# MCPS_Supply_030601.net
KiCad netlist of a schematic drawn in Altium Designer
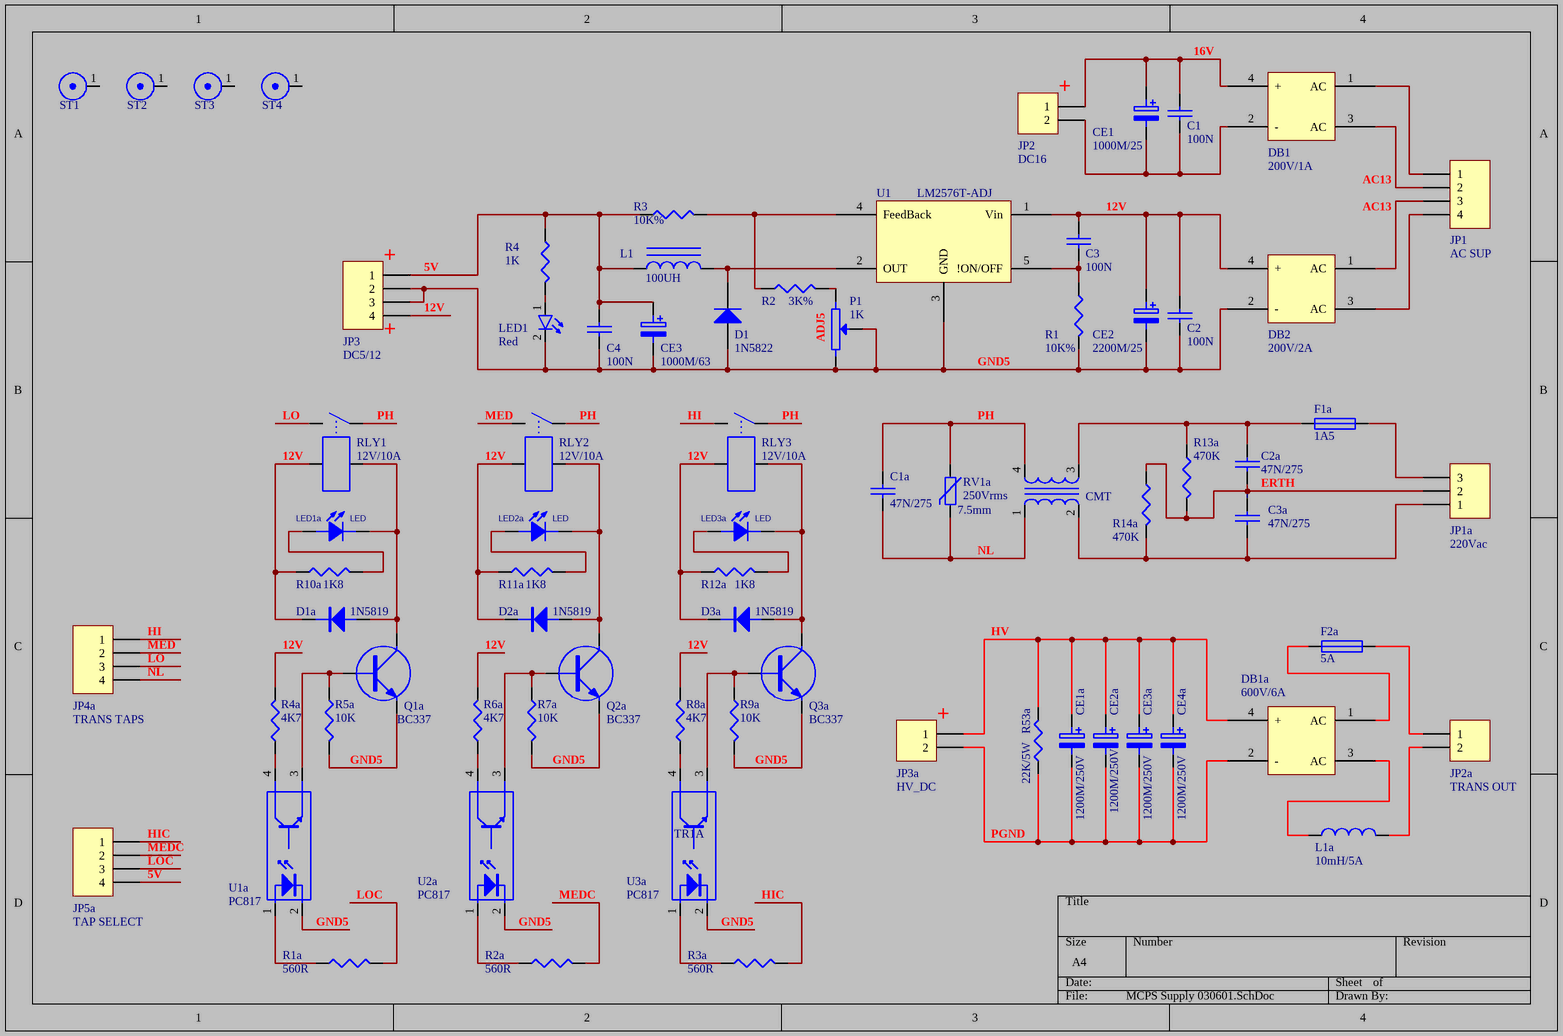
[diagram p0: MCPS Supply 030601.SchDoc]

(export (version "E")
  (design (tool "Eeschema 10.0.6"))
  (components
    (comp (ref "C1") (value "100N") (footprint "c1.8p") (libsource (lib "*") (part "C")))
    (comp (ref "C1a") (value "47N/275") (footprint "47N/275") (libsource (lib "*") (part "C")))
    (comp (ref "C2") (value "100N") (footprint "c1.8p") (libsource (lib "*") (part "C")))
    (comp (ref "C2a") (value "47N/275") (footprint "47N/275") (libsource (lib "*") (part "C")))
    (comp (ref "C3") (value "100N") (footprint "C3P") (libsource (lib "*") (part "C")))
    (comp (ref "C3a") (value "47N/275") (footprint "47N/275") (libsource (lib "*") (part "C")))
    (comp (ref "C4") (value "100N") (footprint "c1.8p") (libsource (lib "*") (part "C")))
    (comp (ref "CE1") (value "1000M/25") (footprint "CAP1000M/25V") (libsource (lib "*") (part "E")))
    (comp (ref "CE1a") (value "1200M/250V") (footprint "CAP 1200M/250") (libsource (lib "*") (part "E")))
    (comp (ref "CE2") (value "2200M/25") (footprint "CAP 2200/25") (libsource (lib "*") (part "E")))
    (comp (ref "CE2a") (value "1200M/250V") (footprint "CAP 1200M/250") (libsource (lib "*") (part "E")))
    (comp (ref "CE3") (value "1000M/63") (footprint "CAP2P") (libsource (lib "*") (part "E")))
    (comp (ref "CE3a") (value "1200M/250V") (footprint "CAP 1200M/250") (libsource (lib "*") (part "E")))
    (comp (ref "CE4a") (value "1200M/250V") (footprint "CAP 1200M/250") (libsource (lib "*") (part "E")))
    (comp (ref "D1")
      (value "1N5822")
      (footprint "d54")
      (description "Default Diode")
      (fields (field (name "PUBLISHER") "Altium Limited"))
      (libsource (lib "Miscellaneous Devices") (part "Diode"))
    )
    (comp (ref "D1a") (value "1N5819") (footprint "D4P") (libsource (lib "MyAltiumLib9702") (part "D")))
    (comp (ref "D2a") (value "1N5819") (footprint "D4P") (libsource (lib "MyAltiumLib9702") (part "D")))
    (comp (ref "D3a") (value "1N5819") (footprint "D4P") (libsource (lib "MyAltiumLib9702") (part "D")))
    (comp (ref "DB1")
      (value "200V/1A")
      (footprint "BRG 1A")
      (libsource (lib "1402 Schlib 2020") (part "BRIDGE"))
    )
    (comp (ref "DB1a")
      (value "600V/6A")
      (footprint "BRIDGE 6A")
      (libsource (lib "1403 Schlib 2020") (part "BRIDGE"))
    )
    (comp (ref "DB2")
      (value "200V/2A")
      (footprint "BRG GBU")
      (libsource (lib "1402 Schlib 2020") (part "BRIDGE"))
    )
    (comp (ref "F1a") (value "1A5") (footprint "FS") (libsource (lib "1402 Schlib 2020") (part "FUSE1")))
    (comp (ref "F2a") (value "5A") (footprint "FS") (libsource (lib "1402 Schlib 2020") (part "FUSE1")))
    (comp (ref "JP1")
      (value "AC SUP")
      (footprint "4EDG")
      (description "Header, 4-Pin")
      (fields (field (name "PUBLISHER") "Altium Limited"))
      (libsource (lib "") (part "Header 4_1"))
    )
    (comp (ref "JP1a")
      (value "220Vac")
      (footprint "3EDG-STR")
      (description "Header, 3-Pin")
      (fields (field (name "PUBLISHER") "Altium Limited"))
      (libsource (lib "1402 Schlib 2020") (part "Header 3"))
    )
    (comp (ref "JP2")
      (value "DC16")
      (footprint "2edg-str")
      (description "Header, 2-Pin")
      (fields (field (name "PUBLISHER") "Altium Limited"))
      (libsource (lib "") (part "Header 2_1"))
    )
    (comp (ref "JP2a")
      (value "TRANS OUT")
      (footprint "2edg-str")
      (description "Header, 2-Pin")
      (fields (field (name "PUBLISHER") "Altium Limited"))
      (libsource (lib "Miscellaneous Connectors") (part "Header 2"))
    )
    (comp (ref "JP3")
      (value "DC5/12")
      (footprint "4EDG")
      (description "Header, 4-Pin")
      (fields (field (name "PUBLISHER") "Altium Limited"))
      (libsource (lib "1403 Schlib 2020") (part "Header 4"))
    )
    (comp (ref "JP3a")
      (value "HV_DC")
      (footprint "DG55X2")
      (description "Header, 2-Pin")
      (fields (field (name "PUBLISHER") "Altium Limited"))
      (libsource (lib "") (part "Header 2_1"))
    )
    (comp (ref "JP4a")
      (value "TRANS TAPS")
      (footprint "4EDG")
      (description "Header, 4-Pin")
      (fields (field (name "PUBLISHER") "Altium Limited"))
      (libsource (lib "1403 Schlib 2020") (part "Header 4"))
    )
    (comp (ref "JP5a")
      (value "TAP SELECT")
      (footprint "4EDG")
      (description "Header, 4-Pin")
      (fields (field (name "PUBLISHER") "Altium Limited"))
      (libsource (lib "1403 Schlib 2020") (part "Header 4"))
    )
    (comp (ref "L1") (value "100UH") (footprint "inductor 2512") (libsource (lib "*") (part "INDUCTOR IRON")))
    (comp (ref "L1a")
      (value "10mH/5A")
      (footprint "INDUCTOR 2208")
      (libsource (lib "MyAltiumLib9702") (part "INDUCTOR"))
    )
    (comp (ref "LED1")
      (value "Red")
      (footprint "LED-5mm")
      (description "LED")
      (fields (field (name "COLOR") "Red") (field (name "DESIGNER") "Saeid Jorablo"))
      (libsource (lib "My Library") (part "LED"))
    )
    (comp (ref "LED1a")
      (value "LED")
      (footprint "LED-5mm")
      (description "LED LIGHTING")
      (fields (field (name "DESIGNER") "Abbas Basereh"))
      (libsource (lib "1403 Schlib 2020") (part "LED"))
    )
    (comp (ref "LED2a")
      (value "LED")
      (footprint "LED-5mm")
      (description "LED LIGHTING")
      (fields (field (name "DESIGNER") "Abbas Basereh"))
      (libsource (lib "1403 Schlib 2020") (part "LED"))
    )
    (comp (ref "LED3a")
      (value "LED")
      (footprint "LED-5mm")
      (description "LED LIGHTING")
      (fields (field (name "DESIGNER") "Abbas Basereh"))
      (libsource (lib "1403 Schlib 2020") (part "LED"))
    )
    (comp (ref "P1")
      (value "1K")
      (footprint "pot multi turn")
      (libsource (lib "1402 Schlib 2020") (part "POT2"))
    )
    (comp (ref "Q1a") (value "BC337") (footprint "CBE-BC546") (libsource (lib "1403 Schlib 2020") (part "N")))
    (comp (ref "Q2a") (value "BC337") (footprint "CBE-BC546") (libsource (lib "1403 Schlib 2020") (part "N")))
    (comp (ref "Q3a") (value "BC337") (footprint "CBE-BC546") (libsource (lib "1403 Schlib 2020") (part "N")))
    (comp (ref "R1") (value "10K%") (footprint "R4P") (libsource (lib "*") (part "R")))
    (comp (ref "R1a") (value "560R") (footprint "R4P") (libsource (lib "*") (part "R")))
    (comp (ref "R2") (value "3K%") (footprint "R4P") (libsource (lib "*") (part "R")))
    (comp (ref "R2a") (value "560R") (footprint "R4P") (libsource (lib "*") (part "R")))
    (comp (ref "R3") (value "10K%") (footprint "R4P") (libsource (lib "*") (part "R")))
    (comp (ref "R3a") (value "560R") (footprint "R4P") (libsource (lib "*") (part "R")))
    (comp (ref "R4") (value "1K") (footprint "R4P") (libsource (lib "*") (part "R")))
    (comp (ref "R4a") (value "4K7") (footprint "R4P") (libsource (lib "*") (part "R")))
    (comp (ref "R5a") (value "10K") (footprint "R4P") (libsource (lib "*") (part "R")))
    (comp (ref "R6a") (value "4K7") (footprint "R4P") (libsource (lib "*") (part "R")))
    (comp (ref "R7a") (value "10K") (footprint "R4P") (libsource (lib "*") (part "R")))
    (comp (ref "R8a") (value "4K7") (footprint "R4P") (libsource (lib "*") (part "R")))
    (comp (ref "R9a") (value "10K") (footprint "R4P") (libsource (lib "*") (part "R")))
    (comp (ref "R10a") (value "1K8") (footprint "R4P") (libsource (lib "*") (part "R")))
    (comp (ref "R11a") (value "1K8") (footprint "R4P") (libsource (lib "*") (part "R")))
    (comp (ref "R12a") (value "1K8") (footprint "R4P") (libsource (lib "*") (part "R")))
    (comp (ref "R13a") (value "470K") (footprint "R5P") (libsource (lib "*") (part "R")))
    (comp (ref "R14a") (value "470K") (footprint "R5P") (libsource (lib "*") (part "R")))
    (comp (ref "R53a") (value "22K/5W") (footprint "R5W") (libsource (lib "*") (part "R")))
    (comp (ref "RLY1")
      (value "12V/10A")
      (footprint "RLY16D")
      (libsource (lib "1403 Schlib 2020") (part "RELAY-SPST4"))
    )
    (comp (ref "RLY2")
      (value "12V/10A")
      (footprint "RLY16D")
      (libsource (lib "1403 Schlib 2020") (part "RELAY-SPST4"))
    )
    (comp (ref "RLY3")
      (value "12V/10A")
      (footprint "RLY16D")
      (libsource (lib "1403 Schlib 2020") (part "RELAY-SPST4"))
    )
    (comp (ref "RV1a")
      (value "250Vrms")
      (footprint "VARISTOR 3")
      (libsource (lib "1402 Schlib 2020") (part "VARISTOR"))
    )
    (comp (ref "ST1") (value "STUD") (footprint "CORNER") (libsource (lib "1402 Schlib 2020") (part "STUD")))
    (comp (ref "ST2") (value "STUD") (footprint "CORNER") (libsource (lib "1402 Schlib 2020") (part "STUD")))
    (comp (ref "ST3") (value "STUD") (footprint "CORNER") (libsource (lib "1402 Schlib 2020") (part "STUD")))
    (comp (ref "ST4") (value "STUD") (footprint "CORNER") (libsource (lib "1402 Schlib 2020") (part "STUD")))
    (comp (ref "TR1A") (value "CMT") (footprint "CMT1") (libsource (lib "1402 Schlib 2020") (part "TRANS1")))
    (comp (ref "U1") (value "LM2576T-ADJ") (footprint "PENTA1") (libsource (lib "*") (part "LM2576")))
    (comp (ref "U1a")
      (value "PC817")
      (footprint "DIP4")
      (libsource (lib "1403 Schlib 2020") (part "OPTODIP4"))
    )
    (comp (ref "U2a")
      (value "PC817")
      (footprint "DIP4")
      (libsource (lib "1403 Schlib 2020") (part "OPTODIP4"))
    )
    (comp (ref "U3a")
      (value "PC817")
      (footprint "DIP4")
      (libsource (lib "1403 Schlib 2020") (part "OPTODIP4"))
    )
  )
  (nets
    (net (code "1") (name "/5V") (class "Default")
      (node (ref "C4") (pin "1") (pintype "passive"))
      (node (ref "CE3") (pin "1") (pintype "passive"))
      (node (ref "JP3") (pin "1") (pinfunction "1_1") (pintype "passive"))
      (node (ref "JP5a") (pin "4") (pinfunction "4_4") (pintype "passive"))
      (node (ref "L1") (pin "1") (pinfunction "1_1") (pintype "passive"))
      (node (ref "R3") (pin "1") (pintype "passive"))
      (node (ref "R4") (pin "1") (pintype "passive"))
    )
    (net (code "2") (name "/12V") (class "Default")
      (node (ref "C2") (pin "1") (pintype "passive"))
      (node (ref "C3") (pin "1") (pintype "passive"))
      (node (ref "CE2") (pin "1") (pintype "passive"))
      (node (ref "D1a") (pin "2") (pinfunction "K_2") (pintype "passive"))
      (node (ref "D2a") (pin "2") (pinfunction "K_2") (pintype "passive"))
      (node (ref "D3a") (pin "2") (pinfunction "K_2") (pintype "passive"))
      (node (ref "DB2") (pin "4") (pinfunction "+_4") (pintype "passive"))
      (node (ref "JP3") (pin "4") (pinfunction "4_4") (pintype "passive"))
      (node (ref "R10a") (pin "1") (pintype "passive"))
      (node (ref "R11a") (pin "1") (pintype "passive"))
      (node (ref "R12a") (pin "1") (pintype "passive"))
      (node (ref "R4a") (pin "2") (pintype "passive"))
      (node (ref "R6a") (pin "2") (pintype "passive"))
      (node (ref "R8a") (pin "2") (pintype "passive"))
      (node (ref "RLY1") (pin "5") (pintype "passive"))
      (node (ref "RLY2") (pin "5") (pintype "passive"))
      (node (ref "RLY3") (pin "5") (pintype "passive"))
      (node (ref "U1") (pin "1") (pinfunction "Vin_1") (pintype "passive"))
    )
    (net (code "3") (name "/16V") (class "Default")
      (node (ref "C1") (pin "1") (pintype "passive"))
      (node (ref "CE1") (pin "1") (pintype "passive"))
      (node (ref "DB1") (pin "4") (pinfunction "+_4") (pintype "passive"))
      (node (ref "JP2") (pin "1") (pinfunction "1_1") (pintype "passive"))
    )
    (net (code "4") (name "/ERTH") (class "Default")
      (node (ref "C2a") (pin "2") (pintype "passive"))
      (node (ref "C3a") (pin "1") (pintype "passive"))
      (node (ref "JP1a") (pin "2") (pinfunction "2_2") (pintype "passive"))
      (node (ref "R13a") (pin "2") (pintype "passive"))
      (node (ref "R14a") (pin "1") (pintype "passive"))
    )
    (net (code "5") (name "/GND5") (class "Default")
      (node (ref "C2") (pin "2") (pintype "passive"))
      (node (ref "C4") (pin "2") (pintype "passive"))
      (node (ref "CE2") (pin "2") (pintype "passive"))
      (node (ref "CE3") (pin "2") (pintype "passive"))
      (node (ref "D1") (pin "1") (pinfunction "A_1") (pintype "passive"))
      (node (ref "DB2") (pin "2") (pinfunction "-_2") (pintype "passive"))
      (node (ref "JP3") (pin "2") (pinfunction "2_2") (pintype "passive"))
      (node (ref "JP3") (pin "3") (pinfunction "3_3") (pintype "passive"))
      (node (ref "LED1") (pin "2") (pinfunction "K_2") (pintype "passive"))
      (node (ref "P1") (pin "2") (pintype "passive"))
      (node (ref "P1") (pin "3") (pintype "passive"))
      (node (ref "Q1a") (pin "1") (pinfunction "E_1") (pintype "passive"))
      (node (ref "Q2a") (pin "1") (pinfunction "E_1") (pintype "passive"))
      (node (ref "Q3a") (pin "1") (pinfunction "E_1") (pintype "passive"))
      (node (ref "R1") (pin "2") (pintype "passive"))
      (node (ref "R5a") (pin "2") (pintype "passive"))
      (node (ref "R7a") (pin "2") (pintype "passive"))
      (node (ref "R9a") (pin "2") (pintype "passive"))
      (node (ref "U1") (pin "3") (pinfunction "GND_3") (pintype "passive"))
      (node (ref "U1a") (pin "2") (pinfunction "K_2") (pintype "passive"))
      (node (ref "U2a") (pin "2") (pinfunction "K_2") (pintype "passive"))
      (node (ref "U3a") (pin "2") (pinfunction "K_2") (pintype "passive"))
    )
    (net (code "6") (name "/HI") (class "Default")
      (node (ref "JP4a") (pin "1") (pinfunction "1_1") (pintype "passive"))
      (node (ref "RLY3") (pin "2") (pintype "passive"))
    )
    (net (code "7") (name "/HIC") (class "Default")
      (node (ref "JP5a") (pin "1") (pinfunction "1_1") (pintype "passive"))
      (node (ref "R3a") (pin "2") (pintype "passive"))
    )
    (net (code "8") (name "/HV") (class "Default")
      (node (ref "CE1a") (pin "1") (pintype "passive"))
      (node (ref "CE2a") (pin "1") (pintype "passive"))
      (node (ref "CE3a") (pin "1") (pintype "passive"))
      (node (ref "CE4a") (pin "1") (pintype "passive"))
      (node (ref "DB1a") (pin "4") (pinfunction "+_4") (pintype "passive"))
      (node (ref "JP3a") (pin "1") (pinfunction "1_1") (pintype "passive"))
      (node (ref "R53a") (pin "2") (pintype "passive"))
    )
    (net (code "9") (name "/LO") (class "Default")
      (node (ref "JP4a") (pin "3") (pinfunction "3_3") (pintype "passive"))
      (node (ref "RLY1") (pin "2") (pintype "passive"))
    )
    (net (code "10") (name "/LOC") (class "Default")
      (node (ref "JP5a") (pin "3") (pinfunction "3_3") (pintype "passive"))
      (node (ref "R1a") (pin "2") (pintype "passive"))
    )
    (net (code "11") (name "/MED") (class "Default")
      (node (ref "JP4a") (pin "2") (pinfunction "2_2") (pintype "passive"))
      (node (ref "RLY2") (pin "2") (pintype "passive"))
    )
    (net (code "12") (name "/MEDC") (class "Default")
      (node (ref "JP5a") (pin "2") (pinfunction "2_2") (pintype "passive"))
      (node (ref "R2a") (pin "2") (pintype "passive"))
    )
    (net (code "13") (name "/NL") (class "Default")
      (node (ref "C1a") (pin "2") (pintype "passive"))
      (node (ref "JP4a") (pin "4") (pinfunction "4_4") (pintype "passive"))
      (node (ref "RV1a") (pin "2") (pinfunction "2_2") (pintype "passive"))
      (node (ref "TR1A") (pin "1") (pintype "passive"))
    )
    (net (code "14") (name "/PGND") (class "Default")
      (node (ref "CE1a") (pin "2") (pintype "passive"))
      (node (ref "CE2a") (pin "2") (pintype "passive"))
      (node (ref "CE3a") (pin "2") (pintype "passive"))
      (node (ref "CE4a") (pin "2") (pintype "passive"))
      (node (ref "DB1a") (pin "2") (pinfunction "-_2") (pintype "passive"))
      (node (ref "JP3a") (pin "2") (pinfunction "2_2") (pintype "passive"))
      (node (ref "R53a") (pin "1") (pintype "passive"))
    )
    (net (code "15") (name "/PH") (class "Default")
      (node (ref "C1a") (pin "1") (pintype "passive"))
      (node (ref "RLY1") (pin "1") (pintype "passive"))
      (node (ref "RLY2") (pin "1") (pintype "passive"))
      (node (ref "RLY3") (pin "1") (pintype "passive"))
      (node (ref "RV1a") (pin "1") (pinfunction "1_1") (pintype "passive"))
      (node (ref "TR1A") (pin "4") (pintype "passive"))
    )
    (net (code "16") (name "Net-(C2a-Pad1)") (class "Default")
      (node (ref "C2a") (pin "1") (pintype "passive"))
      (node (ref "F1a") (pin "2") (pintype "passive"))
      (node (ref "R13a") (pin "1") (pintype "passive"))
      (node (ref "TR1A") (pin "3") (pintype "passive"))
    )
    (net (code "17") (name "Net-(C3a-Pad2)") (class "Default")
      (node (ref "C3a") (pin "2") (pintype "passive"))
      (node (ref "JP1a") (pin "1") (pinfunction "1_1") (pintype "passive"))
      (node (ref "R14a") (pin "2") (pintype "passive"))
      (node (ref "TR1A") (pin "2") (pintype "passive"))
    )
    (net (code "18") (name "Net-(D1-K)") (class "Default")
      (node (ref "D1") (pin "2") (pinfunction "K_2") (pintype "passive"))
      (node (ref "L1") (pin "2") (pinfunction "2_2") (pintype "passive"))
      (node (ref "U1") (pin "2") (pinfunction "OUT_2") (pintype "passive"))
    )
    (net (code "19") (name "Net-(D1a-A)") (class "Default")
      (node (ref "D1a") (pin "1") (pinfunction "A_1") (pintype "passive"))
      (node (ref "LED1a") (pin "2") (pinfunction "CATHODE_2") (pintype "passive"))
      (node (ref "Q1a") (pin "3") (pinfunction "C_3") (pintype "passive"))
      (node (ref "RLY1") (pin "4") (pintype "passive"))
    )
    (net (code "20") (name "Net-(D2a-A)") (class "Default")
      (node (ref "D2a") (pin "1") (pinfunction "A_1") (pintype "passive"))
      (node (ref "LED2a") (pin "2") (pinfunction "CATHODE_2") (pintype "passive"))
      (node (ref "Q2a") (pin "3") (pinfunction "C_3") (pintype "passive"))
      (node (ref "RLY2") (pin "4") (pintype "passive"))
    )
    (net (code "21") (name "Net-(D3a-A)") (class "Default")
      (node (ref "D3a") (pin "1") (pinfunction "A_1") (pintype "passive"))
      (node (ref "LED3a") (pin "2") (pinfunction "CATHODE_2") (pintype "passive"))
      (node (ref "Q3a") (pin "3") (pinfunction "C_3") (pintype "passive"))
      (node (ref "RLY3") (pin "4") (pintype "passive"))
    )
    (net (code "22") (name "Net-(DB1--)") (class "Default")
      (node (ref "C1") (pin "2") (pintype "passive"))
      (node (ref "CE1") (pin "2") (pintype "passive"))
      (node (ref "DB1") (pin "2") (pinfunction "-_2") (pintype "passive"))
      (node (ref "JP2") (pin "2") (pinfunction "2_2") (pintype "passive"))
    )
    (net (code "23") (name "Net-(DB1-AC-Pad1)") (class "Default")
      (node (ref "DB1") (pin "1") (pinfunction "AC_1") (pintype "passive"))
      (node (ref "JP1") (pin "1") (pinfunction "1_1") (pintype "passive"))
    )
    (net (code "24") (name "Net-(DB1-AC-Pad3)") (class "Default")
      (node (ref "DB1") (pin "3") (pinfunction "AC_3") (pintype "passive"))
      (node (ref "JP1") (pin "2") (pinfunction "2_2") (pintype "passive"))
    )
    (net (code "25") (name "Net-(DB1a-AC-Pad1)") (class "Default")
      (node (ref "DB1a") (pin "1") (pinfunction "AC_1") (pintype "passive"))
      (node (ref "F2a") (pin "1") (pintype "passive"))
    )
    (net (code "26") (name "Net-(DB1a-AC-Pad3)") (class "Default")
      (node (ref "DB1a") (pin "3") (pinfunction "AC_3") (pintype "passive"))
      (node (ref "L1a") (pin "1") (pinfunction "1_1") (pintype "passive"))
    )
    (net (code "27") (name "Net-(DB2-AC-Pad1)") (class "Default")
      (node (ref "DB2") (pin "1") (pinfunction "AC_1") (pintype "passive"))
      (node (ref "JP1") (pin "3") (pinfunction "3_3") (pintype "passive"))
    )
    (net (code "28") (name "Net-(DB2-AC-Pad3)") (class "Default")
      (node (ref "DB2") (pin "3") (pinfunction "AC_3") (pintype "passive"))
      (node (ref "JP1") (pin "4") (pinfunction "4_4") (pintype "passive"))
    )
    (net (code "29") (name "Net-(F1a-Pad1)") (class "Default")
      (node (ref "F1a") (pin "1") (pintype "passive"))
      (node (ref "JP1a") (pin "3") (pinfunction "3_3") (pintype "passive"))
    )
    (net (code "30") (name "Net-(F2a-Pad2)") (class "Default")
      (node (ref "F2a") (pin "2") (pintype "passive"))
      (node (ref "JP2a") (pin "1") (pinfunction "1_1") (pintype "passive"))
    )
    (net (code "31") (name "Net-(JP2a-Pad2)") (class "Default")
      (node (ref "JP2a") (pin "2") (pinfunction "2_2") (pintype "passive"))
      (node (ref "L1a") (pin "2") (pinfunction "2_2") (pintype "passive"))
    )
    (net (code "32") (name "Net-(LED1-A)") (class "Default")
      (node (ref "LED1") (pin "1") (pinfunction "A_1") (pintype "passive"))
      (node (ref "R4") (pin "2") (pintype "passive"))
    )
    (net (code "33") (name "Net-(LED1a-ANODE)") (class "Default")
      (node (ref "LED1a") (pin "1") (pinfunction "ANODE_1") (pintype "passive"))
      (node (ref "R10a") (pin "2") (pintype "passive"))
    )
    (net (code "34") (name "Net-(LED2a-ANODE)") (class "Default")
      (node (ref "LED2a") (pin "1") (pinfunction "ANODE_1") (pintype "passive"))
      (node (ref "R11a") (pin "2") (pintype "passive"))
    )
    (net (code "35") (name "Net-(LED3a-ANODE)") (class "Default")
      (node (ref "LED3a") (pin "1") (pinfunction "ANODE_1") (pintype "passive"))
      (node (ref "R12a") (pin "2") (pintype "passive"))
    )
    (net (code "36") (name "Net-(P1-Pad1)") (class "Default")
      (node (ref "P1") (pin "1") (pintype "passive"))
      (node (ref "R2") (pin "2") (pintype "passive"))
    )
    (net (code "37") (name "Net-(Q1a-B)") (class "Default")
      (node (ref "Q1a") (pin "2") (pinfunction "B_2") (pintype "passive"))
      (node (ref "R5a") (pin "1") (pintype "passive"))
      (node (ref "U1a") (pin "3") (pinfunction "E_3") (pintype "passive"))
    )
    (net (code "38") (name "Net-(Q2a-B)") (class "Default")
      (node (ref "Q2a") (pin "2") (pinfunction "B_2") (pintype "passive"))
      (node (ref "R7a") (pin "1") (pintype "passive"))
      (node (ref "U2a") (pin "3") (pinfunction "E_3") (pintype "passive"))
    )
    (net (code "39") (name "Net-(Q3a-B)") (class "Default")
      (node (ref "Q3a") (pin "2") (pinfunction "B_2") (pintype "passive"))
      (node (ref "R9a") (pin "1") (pintype "passive"))
      (node (ref "U3a") (pin "3") (pinfunction "E_3") (pintype "passive"))
    )
    (net (code "40") (name "Net-(U1-!ON{slash}OFF)") (class "Default")
      (node (ref "C3") (pin "2") (pintype "passive"))
      (node (ref "R1") (pin "1") (pintype "passive"))
      (node (ref "U1") (pin "5") (pinfunction "!ON/OFF_5") (pintype "passive"))
    )
    (net (code "41") (name "Net-(U1-FeedBack)") (class "Default")
      (node (ref "R2") (pin "1") (pintype "passive"))
      (node (ref "R3") (pin "2") (pintype "passive"))
      (node (ref "U1") (pin "4") (pinfunction "FeedBack_4") (pintype "passive"))
    )
    (net (code "42") (name "Net-(U1a-A)") (class "Default")
      (node (ref "R1a") (pin "1") (pintype "passive"))
      (node (ref "U1a") (pin "1") (pinfunction "A_1") (pintype "passive"))
    )
    (net (code "43") (name "Net-(U1a-C)") (class "Default")
      (node (ref "R4a") (pin "1") (pintype "passive"))
      (node (ref "U1a") (pin "4") (pinfunction "C_4") (pintype "passive"))
    )
    (net (code "44") (name "Net-(U2a-A)") (class "Default")
      (node (ref "R2a") (pin "1") (pintype "passive"))
      (node (ref "U2a") (pin "1") (pinfunction "A_1") (pintype "passive"))
    )
    (net (code "45") (name "Net-(U2a-C)") (class "Default")
      (node (ref "R6a") (pin "1") (pintype "passive"))
      (node (ref "U2a") (pin "4") (pinfunction "C_4") (pintype "passive"))
    )
    (net (code "46") (name "Net-(U3a-A)") (class "Default")
      (node (ref "R3a") (pin "1") (pintype "passive"))
      (node (ref "U3a") (pin "1") (pinfunction "A_1") (pintype "passive"))
    )
    (net (code "47") (name "Net-(U3a-C)") (class "Default")
      (node (ref "R8a") (pin "1") (pintype "passive"))
      (node (ref "U3a") (pin "4") (pinfunction "C_4") (pintype "passive"))
    )
    (net (code "48") (name "unconnected-(ST1-Pad1)") (class "Default")
      (node (ref "ST1") (pin "1") (pintype "passive"))
    )
    (net (code "49") (name "unconnected-(ST2-Pad1)") (class "Default")
      (node (ref "ST2") (pin "1") (pintype "passive"))
    )
    (net (code "50") (name "unconnected-(ST3-Pad1)") (class "Default")
      (node (ref "ST3") (pin "1") (pintype "passive"))
    )
    (net (code "51") (name "unconnected-(ST4-Pad1)") (class "Default")
      (node (ref "ST4") (pin "1") (pintype "passive"))
    )
  )
)
